# Fri3D_2020_ESP32.net
KiCad netlist of a schematic drawn in Altium Designer
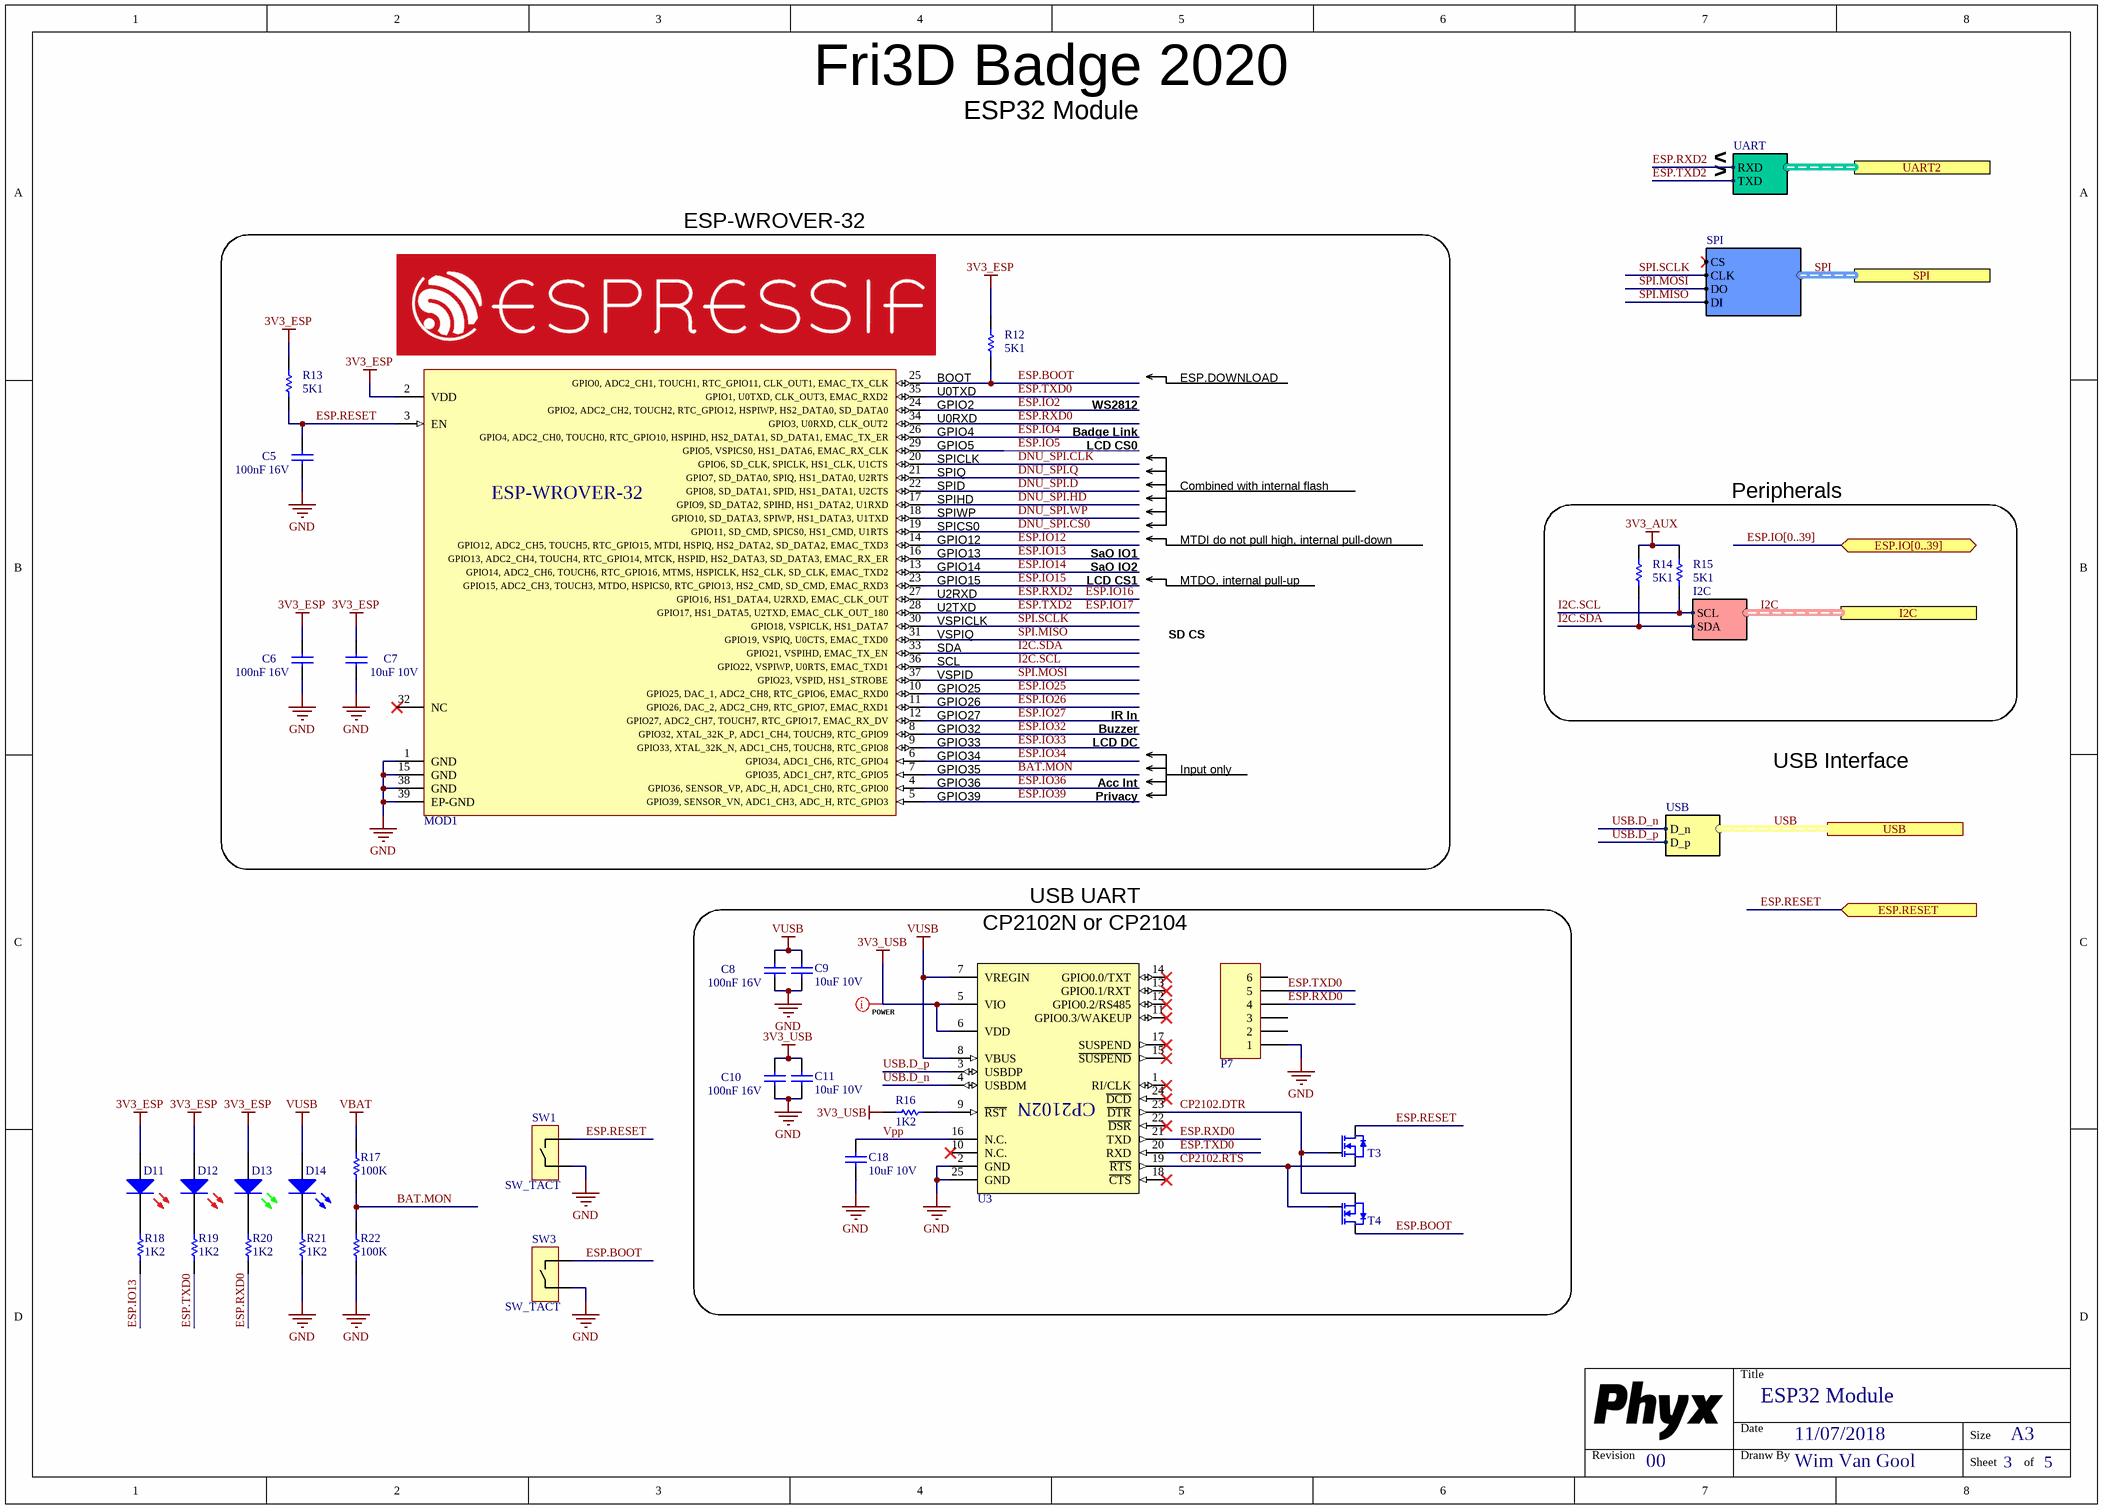
[diagram p0: Fri3D_2020_ESP32.SchDoc]

(export (version "E")
  (design (tool "Eeschema 10.0.6"))
  (components
    (comp (ref "C5")
      (value "100nF 16V")
      (footprint "C0603_N")
      (description "Capacitor Ceramic")
      (libsource (lib "Phyx_Components") (part "CAP_CERAMIC"))
    )
    (comp (ref "C6")
      (value "100nF 16V")
      (footprint "C0603_N")
      (description "Capacitor Ceramic")
      (libsource (lib "Phyx_Components") (part "CAP_CERAMIC"))
    )
    (comp (ref "C7")
      (value "10uF 10V")
      (footprint "C0805_N")
      (description "Capacitor Ceramic")
      (fields (field (name "Comment") "CAP_CERAMIC"))
      (libsource (lib "Phyx_Components") (part "CAP_CERAMIC"))
    )
    (comp (ref "C8")
      (value "100nF 16V")
      (footprint "C0603_N")
      (description "Capacitor Ceramic")
      (libsource (lib "Phyx_Components") (part "CAP_CERAMIC"))
    )
    (comp (ref "C9")
      (value "10uF 10V")
      (footprint "C0805_N")
      (description "Capacitor Ceramic")
      (fields (field (name "Comment") "CAP_CERAMIC"))
      (libsource (lib "Phyx_Components") (part "CAP_CERAMIC"))
    )
    (comp (ref "C10")
      (value "100nF 16V")
      (footprint "C0603_N")
      (description "Capacitor Ceramic")
      (libsource (lib "Phyx_Components") (part "CAP_CERAMIC"))
    )
    (comp (ref "C11")
      (value "10uF 10V")
      (footprint "C0805_N")
      (description "Capacitor Ceramic")
      (fields (field (name "Comment") "CAP_CERAMIC"))
      (libsource (lib "Phyx_Components") (part "CAP_CERAMIC"))
    )
    (comp (ref "C18")
      (value "10uF 10V")
      (footprint "C0805_N")
      (description "Capacitor Ceramic")
      (fields (field (name "Comment") "CAP_CERAMIC"))
      (libsource (lib "Phyx_Components") (part "CAP_CERAMIC"))
    )
    (comp (ref "D11")
      (value "Default 0805 Red LED")
      (footprint "LED_0805_RD")
      (description "=Description")
      (libsource (lib "Phyx_Components") (part "LED_RED"))
    )
    (comp (ref "D12")
      (value "Default 0805 Red LED")
      (footprint "LED_0805_RD")
      (description "=Description")
      (libsource (lib "Phyx_Components") (part "LED_RED"))
    )
    (comp (ref "D13")
      (value "Default 0805 Green LED")
      (footprint "LED_0805_GR")
      (description "=Description")
      (libsource (lib "Phyx_Components") (part "LED_GREEN"))
    )
    (comp (ref "D14")
      (value "Default 0805 Blue LED")
      (footprint "LED_0805_BL")
      (description "=Description")
      (libsource (lib "Phyx_Components") (part "LED_BLUE"))
    )
    (comp (ref "MOD1")
      (value "ESP-32 based ESP-WROVER-32")
      (footprint "ESP-WROVER-32")
      (description "WiFi # MOD ESP-WROVER-32")
      (libsource (lib "Phyx_Components") (part "ESP-WROVER-32"))
    )
    (comp (ref "P7")
      (value "Header 6")
      (footprint "HDR1X6")
      (libsource (lib "Phyx_Components") (part "Header 6"))
    )
    (comp (ref "R12")
      (value "5K1")
      (footprint "R0603_N")
      (fields (field (name "Comment") "RESISTOR"))
      (libsource (lib "Phyx_Components") (part "RESISTOR"))
    )
    (comp (ref "R13")
      (value "5K1")
      (footprint "R0603_N")
      (fields (field (name "Comment") "RESISTOR"))
      (libsource (lib "Phyx_Components") (part "RESISTOR"))
    )
    (comp (ref "R14")
      (value "5K1")
      (footprint "R0603_N")
      (fields (field (name "Comment") "RESISTOR"))
      (libsource (lib "Phyx_Components") (part "RESISTOR"))
    )
    (comp (ref "R15")
      (value "5K1")
      (footprint "R0603_N")
      (fields (field (name "Comment") "RESISTOR"))
      (libsource (lib "Phyx_Components") (part "RESISTOR"))
    )
    (comp (ref "R16")
      (value "1K2")
      (footprint "R0603_N")
      (fields (field (name "Comment") "RESISTOR"))
      (libsource (lib "Phyx_Components") (part "RESISTOR"))
    )
    (comp (ref "R17")
      (value "100K")
      (footprint "R0603_N")
      (fields (field (name "Comment") "RESISTOR"))
      (libsource (lib "Phyx_Components") (part "RESISTOR"))
    )
    (comp (ref "R18")
      (value "1K2")
      (footprint "R0603_N")
      (fields (field (name "Comment") "RESISTOR"))
      (libsource (lib "Phyx_Components") (part "RESISTOR"))
    )
    (comp (ref "R19")
      (value "1K2")
      (footprint "R0603_N")
      (fields (field (name "Comment") "RESISTOR"))
      (libsource (lib "Phyx_Components") (part "RESISTOR"))
    )
    (comp (ref "R20")
      (value "1K2")
      (footprint "R0603_N")
      (fields (field (name "Comment") "RESISTOR"))
      (libsource (lib "Phyx_Components") (part "RESISTOR"))
    )
    (comp (ref "R21")
      (value "1K2")
      (footprint "R0603_N")
      (fields (field (name "Comment") "RESISTOR"))
      (libsource (lib "Phyx_Components") (part "RESISTOR"))
    )
    (comp (ref "R22")
      (value "100K")
      (footprint "R0603_N")
      (fields (field (name "Comment") "RESISTOR"))
      (libsource (lib "Phyx_Components") (part "RESISTOR"))
    )
    (comp (ref "SW1")
      (value "SW_TACT")
      (footprint "WE_430181038816")
      (libsource (lib "Phyx_Components") (part "SW_TACT"))
    )
    (comp (ref "SW3")
      (value "SW_TACT")
      (footprint "WE_430181038816")
      (libsource (lib "Phyx_Components") (part "SW_TACT"))
    )
    (comp (ref "T3")
      (value "0.2A N-Ch MOSFET Vgs 3.2")
      (footprint "SOT23-3")
      (libsource (lib "Phyx_Components") (part "N_MOSFET_GSD"))
    )
    (comp (ref "T4")
      (value "0.2A N-Ch MOSFET Vgs 3.2")
      (footprint "SOT23-3")
      (libsource (lib "Phyx_Components") (part "N_MOSFET_GSD"))
    )
    (comp (ref "U3")
      (value "USB to UART 3.3-5V")
      (footprint "QFN_24")
      (description "=Description")
      (libsource (lib "Phyx_Components") (part "CP2102N_QFN24"))
    )
  )
  (nets
    (net (code "28") (name "/BAT.MON") (class "Default")
      (node (ref "MOD1") (pin "7") (pinfunction "GPIO35,_ADC1_CH7,_RTC_GPIO5_7") (pintype "input"))
      (node (ref "R17") (pin "2") (pinfunction "2_2") (pintype "passive"))
      (node (ref "R22") (pin "1") (pinfunction "1_1") (pintype "passive"))
    )
    (net (code "29") (name "/CP2102.DTR") (class "Default")
      (node (ref "T3") (pin "1") (pinfunction "G_1") (pintype "passive"))
      (node (ref "T4") (pin "2") (pinfunction "S_2") (pintype "passive"))
      (node (ref "U3") (pin "23") (pinfunction "~{DTR}_23") (pintype "output"))
    )
    (net (code "30") (name "/CP2102.RTS") (class "Default")
      (node (ref "T3") (pin "2") (pinfunction "S_2") (pintype "passive"))
      (node (ref "T4") (pin "1") (pinfunction "G_1") (pintype "passive"))
      (node (ref "U3") (pin "19") (pinfunction "~{RTS}_19") (pintype "output"))
    )
    (net (code "31") (name "/DNU_SPI.CLK") (class "Default")
      (node (ref "MOD1") (pin "20") (pinfunction "GPIO6,_SD_CLK,_SPICLK,_HS1_CLK,_U1CTS_20") (pintype "bidirectional"))
    )
    (net (code "32") (name "/DNU_SPI.CS0") (class "Default")
      (node (ref "MOD1") (pin "19") (pinfunction "GPIO11,_SD_CMD,_SPICS0,_HS1_CMD,_U1RTS_19") (pintype "bidirectional"))
    )
    (net (code "33") (name "/DNU_SPI.D") (class "Default")
      (node (ref "MOD1") (pin "22") (pinfunction "GPIO8,_SD_DATA1,_SPID,_HS1_DATA1,_U2CTS_22") (pintype "bidirectional"))
    )
    (net (code "34") (name "/DNU_SPI.HD") (class "Default")
      (node (ref "MOD1") (pin "17") (pinfunction "GPIO9,_SD_DATA2,_SPIHD,_HS1_DATA2,_U1RXD_17") (pintype "bidirectional"))
    )
    (net (code "35") (name "/DNU_SPI.Q") (class "Default")
      (node (ref "MOD1") (pin "21") (pinfunction "GPIO7,_SD_DATA0,_SPIQ,_HS1_DATA0,_U2RTS_21") (pintype "bidirectional"))
    )
    (net (code "36") (name "/DNU_SPI.WP") (class "Default")
      (node (ref "MOD1") (pin "18") (pinfunction "GPIO10,_SD_DATA3,_SPIWP,_HS1_DATA3,_U1TXD_18") (pintype "bidirectional"))
    )
    (net (code "37") (name "/ESP.BOOT") (class "Default")
      (node (ref "MOD1") (pin "25") (pinfunction "GPIO0,_ADC2_CH1,_TOUCH1,_RTC_GPIO11,_CLK_OUT1,_EMAC_TX_CLK_25") (pintype "bidirectional"))
      (node (ref "R12") (pin "2") (pinfunction "2_2") (pintype "passive"))
      (node (ref "SW3") (pin "1") (pinfunction "1_1") (pintype "passive"))
      (node (ref "T4") (pin "3") (pinfunction "D_3") (pintype "passive"))
    )
    (net (code "38") (name "/ESP.IO2") (class "Default")
      (node (ref "MOD1") (pin "24") (pinfunction "GPIO2,_ADC2_CH2,_TOUCH2,_RTC_GPIO12,_HSPIWP,_HS2_DATA0,_SD_DATA0_24") (pintype "bidirectional"))
    )
    (net (code "39") (name "/ESP.IO4") (class "Default")
      (node (ref "MOD1") (pin "26") (pinfunction "GPIO4,_ADC2_CH0,_TOUCH0,_RTC_GPIO10,_HSPIHD,_HS2_DATA1,_SD_DATA1,_EMAC_TX_ER_26") (pintype "bidirectional"))
    )
    (net (code "40") (name "/ESP.IO5") (class "Default")
      (node (ref "MOD1") (pin "29") (pinfunction "GPIO5,_VSPICS0,_HS1_DATA6,_EMAC_RX_CLK_29") (pintype "bidirectional"))
    )
    (net (code "41") (name "/ESP.IO12") (class "Default")
      (node (ref "MOD1") (pin "14") (pinfunction "GPIO12,_ADC2_CH5,_TOUCH5,_RTC_GPIO15,_MTDI,_HSPIQ,_HS2_DATA2,_SD_DATA2,_EMAC_TXD3_14") (pintype "bidirectional"))
    )
    (net (code "42") (name "/ESP.IO13") (class "Default")
      (node (ref "MOD1") (pin "16") (pinfunction "GPIO13,_ADC2_CH4,_TOUCH4,_RTC_GPIO14,_MTCK,_HSPID,_HS2_DATA3,_SD_DATA3,_EMAC_RX_ER_16") (pintype "bidirectional"))
      (node (ref "R18") (pin "2") (pinfunction "2_2") (pintype "passive"))
    )
    (net (code "43") (name "/ESP.IO14") (class "Default")
      (node (ref "MOD1") (pin "13") (pinfunction "GPIO14,_ADC2_CH6,_TOUCH6,_RTC_GPIO16,_MTMS,_HSPICLK,_HS2_CLK,_SD_CLK,_EMAC_TXD2_13") (pintype "bidirectional"))
    )
    (net (code "44") (name "/ESP.IO15") (class "Default")
      (node (ref "MOD1") (pin "23") (pinfunction "GPIO15,_ADC2_CH3,_TOUCH3,_MTDO,_HSPICS0,_RTC_GPIO13,_HS2_CMD,_SD_CMD,_EMAC_RXD3_23") (pintype "bidirectional"))
    )
    (net (code "45") (name "/ESP.IO16") (class "Default")
      (node (ref "MOD1") (pin "27") (pinfunction "GPIO16,_HS1_DATA4,_U2RXD,_EMAC_CLK_OUT_27") (pintype "bidirectional"))
    )
    (net (code "46") (name "/ESP.IO17") (class "Default")
      (node (ref "MOD1") (pin "28") (pinfunction "GPIO17,_HS1_DATA5,_U2TXD,_EMAC_CLK_OUT_180_28") (pintype "bidirectional"))
    )
    (net (code "47") (name "/ESP.IO25") (class "Default")
      (node (ref "MOD1") (pin "10") (pinfunction "GPIO25,_DAC_1,_ADC2_CH8,_RTC_GPIO6,_EMAC_RXD0_10") (pintype "bidirectional"))
    )
    (net (code "48") (name "/ESP.IO26") (class "Default")
      (node (ref "MOD1") (pin "11") (pinfunction "GPIO26,_DAC_2,_ADC2_CH9,_RTC_GPIO7,_EMAC_RXD1_11") (pintype "bidirectional"))
    )
    (net (code "49") (name "/ESP.IO27") (class "Default")
      (node (ref "MOD1") (pin "12") (pinfunction "GPIO27,_ADC2_CH7,_TOUCH7,_RTC_GPIO17,_EMAC_RX_DV_12") (pintype "bidirectional"))
    )
    (net (code "50") (name "/ESP.IO32") (class "Default")
      (node (ref "MOD1") (pin "8") (pinfunction "GPIO32,_XTAL_32K_P,_ADC1_CH4,_TOUCH9,_RTC_GPIO9_8") (pintype "bidirectional"))
    )
    (net (code "51") (name "/ESP.IO33") (class "Default")
      (node (ref "MOD1") (pin "9") (pinfunction "GPIO33,_XTAL_32K_N,_ADC1_CH5,_TOUCH8,_RTC_GPIO8_9") (pintype "bidirectional"))
    )
    (net (code "52") (name "/ESP.IO34") (class "Default")
      (node (ref "MOD1") (pin "6") (pinfunction "GPIO34,_ADC1_CH6,_RTC_GPIO4_6") (pintype "input"))
    )
    (net (code "53") (name "/ESP.IO36") (class "Default")
      (node (ref "MOD1") (pin "4") (pinfunction "GPIO36,_SENSOR_VP,_ADC_H,_ADC1_CH0,_RTC_GPIO0_4") (pintype "input"))
    )
    (net (code "54") (name "/ESP.IO39") (class "Default")
      (node (ref "MOD1") (pin "5") (pinfunction "GPIO39,_SENSOR_VN,_ADC1_CH3,_ADC_H,_RTC_GPIO3_5") (pintype "input"))
    )
    (net (code "56") (name "/ESP.RESET") (class "Default")
      (node (ref "C5") (pin "1") (pinfunction "1_1") (pintype "passive"))
      (node (ref "MOD1") (pin "3") (pinfunction "EN_3") (pintype "input"))
      (node (ref "R13") (pin "2") (pinfunction "2_2") (pintype "passive"))
      (node (ref "SW1") (pin "1") (pinfunction "1_1") (pintype "passive"))
      (node (ref "T3") (pin "3") (pinfunction "D_3") (pintype "passive"))
    )
    (net (code "57") (name "/ESP.RXD0") (class "Default")
      (node (ref "MOD1") (pin "34") (pinfunction "GPIO3,_U0RXD,_CLK_OUT2_34") (pintype "bidirectional"))
      (node (ref "P7") (pin "4") (pinfunction "4_4") (pintype "passive"))
      (node (ref "R20") (pin "2") (pinfunction "2_2") (pintype "passive"))
      (node (ref "U3") (pin "21") (pinfunction "TXD_21") (pintype "output"))
    )
    (net (code "58") (name "/ESP.TXD0") (class "Default")
      (node (ref "MOD1") (pin "35") (pinfunction "GPIO1,_U0TXD,_CLK_OUT3,_EMAC_RXD2_35") (pintype "bidirectional"))
      (node (ref "P7") (pin "5") (pinfunction "5_5") (pintype "passive"))
      (node (ref "R19") (pin "2") (pinfunction "2_2") (pintype "passive"))
      (node (ref "U3") (pin "20") (pinfunction "RXD_20") (pintype "input"))
    )
    (net (code "59") (name "/I2C.SCL") (class "Default")
      (node (ref "MOD1") (pin "36") (pinfunction "GPIO22,_VSPIWP,_U0RTS,_EMAC_TXD1_36") (pintype "bidirectional"))
      (node (ref "R15") (pin "2") (pinfunction "2_2") (pintype "passive"))
    )
    (net (code "60") (name "/I2C.SDA") (class "Default")
      (node (ref "MOD1") (pin "33") (pinfunction "GPIO21,_VSPIHD,_EMAC_TX_EN_33") (pintype "bidirectional"))
      (node (ref "R14") (pin "2") (pinfunction "2_2") (pintype "passive"))
    )
    (net (code "62") (name "/SPI.MISO") (class "Default")
      (node (ref "MOD1") (pin "31") (pinfunction "GPIO19,_VSPIQ,_U0CTS,_EMAC_TXD0_31") (pintype "bidirectional"))
    )
    (net (code "63") (name "/SPI.MOSI") (class "Default")
      (node (ref "MOD1") (pin "37") (pinfunction "GPIO23,_VSPID,_HS1_STROBE_37") (pintype "bidirectional"))
    )
    (net (code "64") (name "/SPI.SCLK") (class "Default")
      (node (ref "MOD1") (pin "30") (pinfunction "GPIO18,_VSPICLK,_HS1_DATA7_30") (pintype "bidirectional"))
    )
    (net (code "66") (name "/USB.D_n") (class "Default")
      (node (ref "U3") (pin "4") (pinfunction "USBDM_4") (pintype "bidirectional"))
    )
    (net (code "67") (name "/USB.D_p") (class "Default")
      (node (ref "U3") (pin "3") (pinfunction "USBDP_3") (pintype "bidirectional"))
    )
    (net (code "69") (name "/Vpp") (class "Default")
      (node (ref "C18") (pin "2") (pinfunction "2_2") (pintype "passive"))
      (node (ref "U3") (pin "16") (pinfunction "N.C._16") (pintype "passive"))
    )
    (net (code "71") (name "3V3_AUX") (class "Default")
      (node (ref "R14") (pin "1") (pinfunction "1_1") (pintype "passive"))
      (node (ref "R15") (pin "1") (pinfunction "1_1") (pintype "passive"))
    )
    (net (code "72") (name "3V3_ESP") (class "Default")
      (node (ref "C6") (pin "1") (pinfunction "1_1") (pintype "passive"))
      (node (ref "C7") (pin "1") (pinfunction "1_1") (pintype "passive"))
      (node (ref "D11") (pin "1") (pinfunction "A_1") (pintype "passive"))
      (node (ref "D12") (pin "1") (pinfunction "A_1") (pintype "passive"))
      (node (ref "D13") (pin "1") (pinfunction "A_1") (pintype "passive"))
      (node (ref "MOD1") (pin "2") (pinfunction "VDD_2") (pintype "power_in"))
      (node (ref "R12") (pin "1") (pinfunction "1_1") (pintype "passive"))
      (node (ref "R13") (pin "1") (pinfunction "1_1") (pintype "passive"))
    )
    (net (code "73") (name "3V3_USB") (class "Default")
      (node (ref "C10") (pin "1") (pinfunction "1_1") (pintype "passive"))
      (node (ref "C11") (pin "2") (pinfunction "2_2") (pintype "passive"))
      (node (ref "R16") (pin "1") (pinfunction "1_1") (pintype "passive"))
      (node (ref "U3") (pin "5") (pinfunction "VIO_5") (pintype "power_in"))
      (node (ref "U3") (pin "6") (pinfunction "VDD_6") (pintype "power_in"))
    )
    (net (code "74") (name "GND") (class "Default")
      (node (ref "C10") (pin "2") (pinfunction "2_2") (pintype "passive"))
      (node (ref "C11") (pin "1") (pinfunction "1_1") (pintype "passive"))
      (node (ref "C18") (pin "1") (pinfunction "1_1") (pintype "passive"))
      (node (ref "C5") (pin "2") (pinfunction "2_2") (pintype "passive"))
      (node (ref "C6") (pin "2") (pinfunction "2_2") (pintype "passive"))
      (node (ref "C7") (pin "2") (pinfunction "2_2") (pintype "passive"))
      (node (ref "C8") (pin "2") (pinfunction "2_2") (pintype "passive"))
      (node (ref "C9") (pin "1") (pinfunction "1_1") (pintype "passive"))
      (node (ref "MOD1") (pin "1") (pinfunction "GND_1") (pintype "power_in"))
      (node (ref "MOD1") (pin "15") (pinfunction "GND_15") (pintype "power_in"))
      (node (ref "MOD1") (pin "38") (pinfunction "GND_38") (pintype "power_in"))
      (node (ref "MOD1") (pin "39") (pinfunction "EP-GND_39") (pintype "power_in"))
      (node (ref "P7") (pin "1") (pinfunction "1_1") (pintype "passive"))
      (node (ref "R21") (pin "2") (pinfunction "2_2") (pintype "passive"))
      (node (ref "R22") (pin "2") (pinfunction "2_2") (pintype "passive"))
      (node (ref "SW1") (pin "2") (pinfunction "2_2") (pintype "passive"))
      (node (ref "SW3") (pin "2") (pinfunction "2_2") (pintype "passive"))
      (node (ref "U3") (pin "2") (pinfunction "GND_2") (pintype "power_in"))
      (node (ref "U3") (pin "25") (pinfunction "GND_25") (pintype "power_in"))
    )
    (net (code "75") (name "Net-(D11-K)") (class "Default")
      (node (ref "D11") (pin "2") (pinfunction "K_2") (pintype "passive"))
      (node (ref "R18") (pin "1") (pinfunction "1_1") (pintype "passive"))
    )
    (net (code "76") (name "Net-(D12-K)") (class "Default")
      (node (ref "D12") (pin "2") (pinfunction "K_2") (pintype "passive"))
      (node (ref "R19") (pin "1") (pinfunction "1_1") (pintype "passive"))
    )
    (net (code "77") (name "Net-(D13-K)") (class "Default")
      (node (ref "D13") (pin "2") (pinfunction "K_2") (pintype "passive"))
      (node (ref "R20") (pin "1") (pinfunction "1_1") (pintype "passive"))
    )
    (net (code "78") (name "Net-(D14-K)") (class "Default")
      (node (ref "D14") (pin "2") (pinfunction "K_2") (pintype "passive"))
      (node (ref "R21") (pin "1") (pinfunction "1_1") (pintype "passive"))
    )
    (net (code "79") (name "Net-(U3-~{RST})") (class "Default")
      (node (ref "R16") (pin "2") (pinfunction "2_2") (pintype "passive"))
      (node (ref "U3") (pin "9") (pinfunction "~{RST}_9") (pintype "input"))
    )
    (net (code "80") (name "VBAT") (class "Default")
      (node (ref "R17") (pin "1") (pinfunction "1_1") (pintype "passive"))
    )
    (net (code "81") (name "VUSB") (class "Default")
      (node (ref "C8") (pin "1") (pinfunction "1_1") (pintype "passive"))
      (node (ref "C9") (pin "2") (pinfunction "2_2") (pintype "passive"))
      (node (ref "D14") (pin "1") (pinfunction "A_1") (pintype "passive"))
      (node (ref "U3") (pin "7") (pinfunction "VREGIN_7") (pintype "power_in"))
      (node (ref "U3") (pin "8") (pinfunction "VBUS_8") (pintype "input"))
    )
    (net (code "82") (name "unconnected-(MOD1-NC-Pad32)") (class "Default")
      (node (ref "MOD1") (pin "32") (pinfunction "NC_32") (pintype "passive+no_connect"))
    )
    (net (code "83") (name "unconnected-(P7-Pad2)") (class "Default")
      (node (ref "P7") (pin "2") (pinfunction "2_2") (pintype "passive"))
    )
    (net (code "84") (name "unconnected-(P7-Pad3)") (class "Default")
      (node (ref "P7") (pin "3") (pinfunction "3_3") (pintype "passive"))
    )
    (net (code "85") (name "unconnected-(P7-Pad6)") (class "Default")
      (node (ref "P7") (pin "6") (pinfunction "6_6") (pintype "passive"))
    )
    (net (code "86") (name "unconnected-(U3-GPIO0.0{slash}TXT-Pad14)") (class "Default")
      (node (ref "U3") (pin "14") (pinfunction "GPIO0.0/TXT_14") (pintype "bidirectional+no_connect"))
    )
    (net (code "87") (name "unconnected-(U3-GPIO0.1{slash}RXT-Pad13)") (class "Default")
      (node (ref "U3") (pin "13") (pinfunction "GPIO0.1/RXT_13") (pintype "bidirectional+no_connect"))
    )
    (net (code "88") (name "unconnected-(U3-GPIO0.2{slash}RS485-Pad12)") (class "Default")
      (node (ref "U3") (pin "12") (pinfunction "GPIO0.2/RS485_12") (pintype "bidirectional+no_connect"))
    )
    (net (code "89") (name "unconnected-(U3-GPIO0.3{slash}WAKEUP-Pad11)") (class "Default")
      (node (ref "U3") (pin "11") (pinfunction "GPIO0.3/WAKEUP_11") (pintype "bidirectional+no_connect"))
    )
    (net (code "90") (name "unconnected-(U3-N.C.-Pad10)") (class "Default")
      (node (ref "U3") (pin "10") (pinfunction "N.C._10") (pintype "passive+no_connect"))
    )
    (net (code "91") (name "unconnected-(U3-RI{slash}CLK-Pad1)") (class "Default")
      (node (ref "U3") (pin "1") (pinfunction "RI/CLK_1") (pintype "bidirectional+no_connect"))
    )
    (net (code "92") (name "unconnected-(U3-SUSPEND-Pad17)") (class "Default")
      (node (ref "U3") (pin "17") (pinfunction "SUSPEND_17") (pintype "output+no_connect"))
    )
    (net (code "93") (name "unconnected-(U3-~{CTS}-Pad18)") (class "Default")
      (node (ref "U3") (pin "18") (pinfunction "~{CTS}_18") (pintype "input+no_connect"))
    )
    (net (code "94") (name "unconnected-(U3-~{DCD}-Pad24)") (class "Default")
      (node (ref "U3") (pin "24") (pinfunction "~{DCD}_24") (pintype "input+no_connect"))
    )
    (net (code "95") (name "unconnected-(U3-~{DSR}-Pad22)") (class "Default")
      (node (ref "U3") (pin "22") (pinfunction "~{DSR}_22") (pintype "input+no_connect"))
    )
    (net (code "96") (name "unconnected-(U3-~{SUSPEND}-Pad15)") (class "Default")
      (node (ref "U3") (pin "15") (pinfunction "~{SUSPEND}_15") (pintype "output+no_connect"))
    )
  )
)
